# Power.net
KiCad netlist of a schematic drawn in Altium Designer
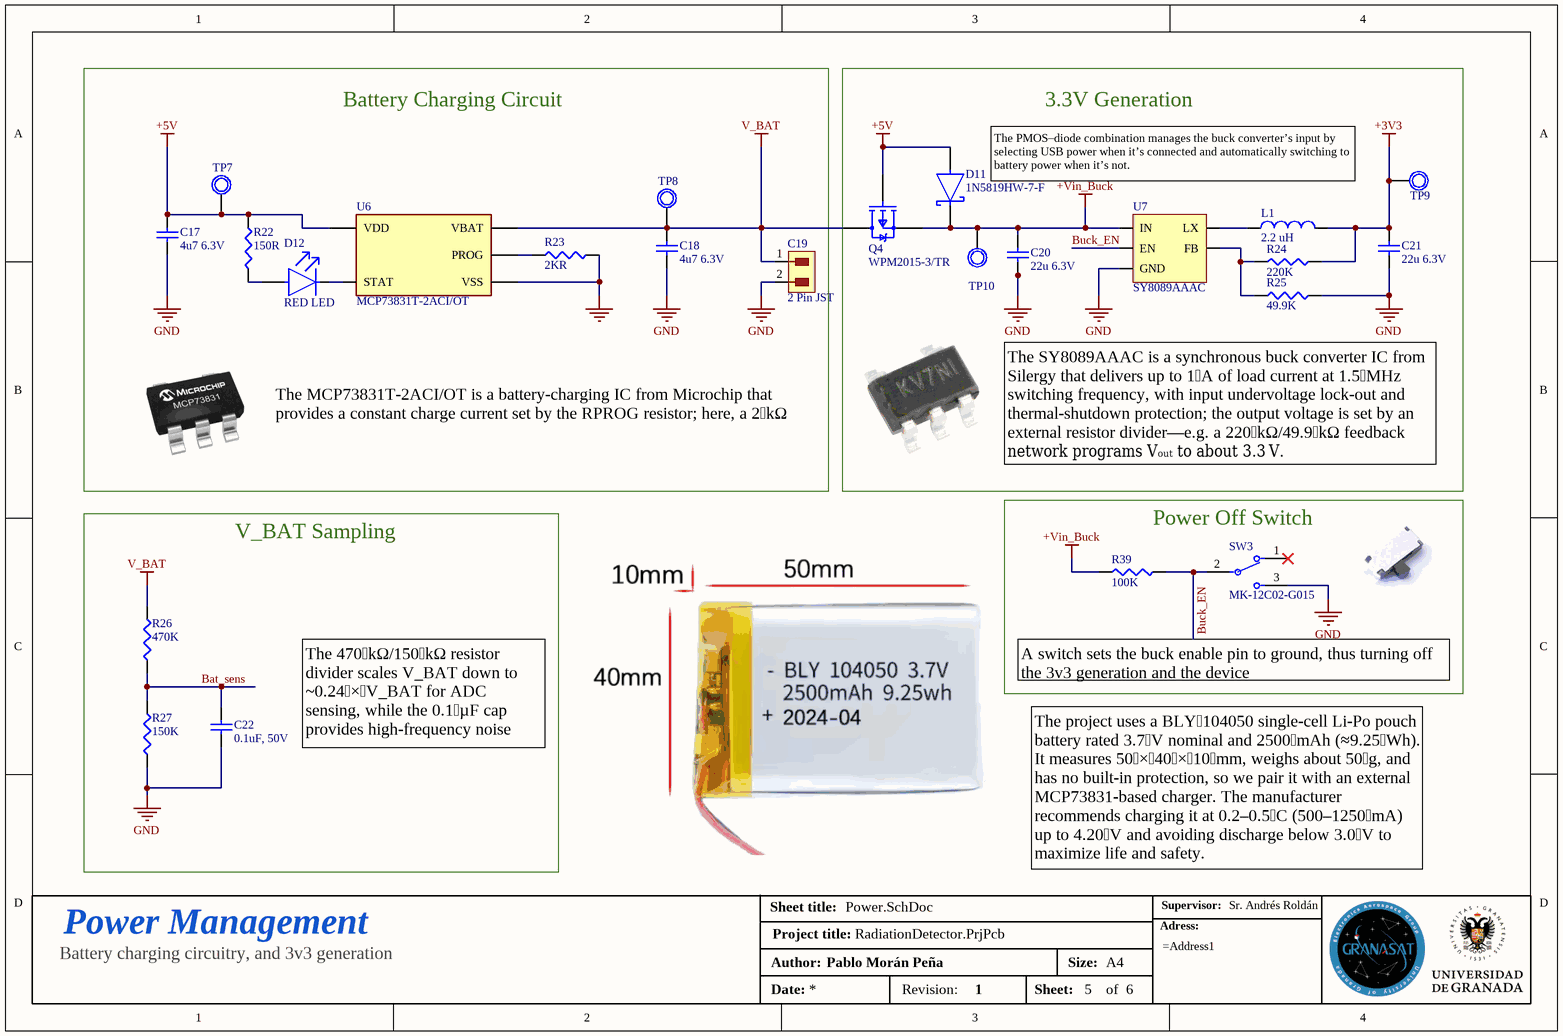
[diagram p0: Power.SchDoc]

(export (version "E")
  (design (tool "Eeschema 10.0.6"))
  (components
    (comp (ref "C17")
      (value "4u7 6.3V")
      (footprint "CAP 0402_1005")
      (description "CAP CER 4.7UF 6.3V X5R 0402")
      (fields
        (field (name "MANUFACTURER") "Samsung")
        (field (name "MANUFACTURER PART NUMBER") "CL05A475KQ5NRNC")
      )
      (libsource (lib "Schlib") (part "CL05A475KQ5NRNC"))
    )
    (comp (ref "C18")
      (value "4u7 6.3V")
      (footprint "CAP 0402_1005")
      (description "CAP CER 4.7UF 6.3V X5R 0402")
      (fields
        (field (name "MANUFACTURER") "Samsung")
        (field (name "MANUFACTURER PART NUMBER") "CL05A475KQ5NRNC")
      )
      (libsource (lib "Schlib") (part "CL05A475KQ5NRNC"))
    )
    (comp (ref "C19")
      (value "2 Pin JST")
      (footprint "JST_B2B-PH-K-S")
      (fields
        (field (name "MANUFACTURER") "JST")
        (field (name "MANUFACTURER PART NUMBER") "B2B-PH-K-S(LF)(SN)")
        (field (name "LCSC PART NUMBER") "C131337")
      )
      (libsource (lib "Schlib") (part "B2B-PH-K-S(LF)(SN)"))
    )
    (comp (ref "C20")
      (value "22u 6.3V")
      (footprint "CAPC1608X90")
      (description "CAP CER 22UF 6.3V X5R 0603")
      (fields
        (field (name "MANUFACTURER") "Samsung")
        (field (name "MANUFACTURER PART NUMBER") "CL10A226MQ8NRNC")
      )
      (libsource (lib "Schlib") (part "CL10A226MQ8NRNC"))
    )
    (comp (ref "C21")
      (value "22u 6.3V")
      (footprint "CAPC1608X90")
      (description "CAP CER 22UF 6.3V X5R 0603")
      (fields
        (field (name "MANUFACTURER") "Samsung")
        (field (name "MANUFACTURER PART NUMBER") "CL10A226MQ8NRNC")
      )
      (libsource (lib "Schlib") (part "CL10A226MQ8NRNC"))
    )
    (comp (ref "C22")
      (value "0.1uF, 50V")
      (footprint "CAP 0402_1005")
      (description "CAP CER 0.1UF 50V X7R 0402")
      (fields
        (field (name "MANUFACTURER") "Samsung")
        (field (name "MANUFACTURER PART NUMBER") "CL05B104KB5NNNC")
      )
      (libsource (lib "Schlib") (part "CL05B104KB5NNNC"))
    )
    (comp (ref "D11")
      (value "1N5819HW-7-F")
      (footprint "FP-SOD123-MFG")
      (description "DIODE SCHOTTKY 40V 1A SOD123")
      (fields (field (name "MANUFACTURER") "Diodes") (field (name "LCSC PART NUMBER") "C82544"))
      (libsource (lib "Schlib") (part "1N5819HW-7-F"))
    )
    (comp (ref "D12")
      (value "RED LED")
      (footprint "FP-LTST-C171KGKT-MFG")
      (description "LED RED CLEAR SMD")
      (fields
        (field (name "MANUFACTURER") "Vishay Lite-On")
        (field (name "MANUFACTURER PART NUMBER") "LTST-C171KGKT")
      )
      (libsource (lib "Schlib") (part "LTST-C171KGKT"))
    )
    (comp (ref "L1")
      (value "2.2 uH")
      (footprint "IND_VLS3015ET-220M-CA")
      (description "1.35A 2.2uH ±20% 1.35A SMD,3x3mm Power Inductors ROHS")
      (fields (field (name "MANUFACTURER") "TDK") (field (name "MANUFACTURER PART NUMBER") "VLS3015ET-2R2M"))
      (libsource (lib "Schlib") (part "VLS3015ET-2R2M"))
    )
    (comp (ref "Q4")
      (value "WPM2015-3/TR")
      (footprint "SOT-23")
      (description "20V 2.4A 110mΩ@4.5V,2.7A 1.1W 1V@250uA 1 P-Channel SOT-23-3 MOSFETs ROHS")
      (fields (field (name "LCSC PART NUMBER") "C6562215"))
      (libsource (lib "Schlib") (part "WPM2015-3/TR"))
    )
    (comp (ref "R22")
      (value "150R")
      (footprint "RESC1005X37N")
      (description "RES SMD 150 OHM 1% 1/16W 0402")
      (fields
        (field (name "MANUFACTURER") "Yageo")
        (field (name "MANUFACTURER PART NUMBER") "AC0402FR-07150RL")
      )
      (libsource (lib "Schlib") (part "AC0402FR-07150RL"))
    )
    (comp (ref "R23")
      (value "2KR")
      (footprint "RESC1005X37N")
      (description "RES 2K OHM 1% 1/16W 0402")
      (fields
        (field (name "MANUFACTURER") "Yageo")
        (field (name "MANUFACTURER PART NUMBER") "AC0402FR-132KL")
      )
      (libsource (lib "Schlib") (part "AC0402FR-132KL"))
    )
    (comp (ref "R24")
      (value "220K")
      (footprint "RESC1005X37N")
      (description "RES 220K OHM 5% 1/16W 0402")
      (fields
        (field (name "MANUFACTURER") "Yageo")
        (field (name "MANUFACTURER PART NUMBER") "RC0402JR-07220KL")
      )
      (libsource (lib "Schlib") (part "RC0402JR-07220KL"))
    )
    (comp (ref "R25")
      (value "49.9K")
      (footprint "RESC1005X37N")
      (description "RES 49.9K OHM 1% 1/16W 0402")
      (fields
        (field (name "MANUFACTURER") "Yageo")
        (field (name "MANUFACTURER PART NUMBER") "RC0402FR-0749K9L")
      )
      (libsource (lib "Schlib") (part "RC0402FR-0749K9L"))
    )
    (comp (ref "R26")
      (value "470K")
      (footprint "RESC1005X37N")
      (description "RES 470K OHM 5% 1/16W 0402")
      (fields
        (field (name "MANUFACTURER") "Yageo")
        (field (name "MANUFACTURER PART NUMBER") "RC0402JR-07470KL")
      )
      (libsource (lib "Schlib") (part "RC0402JR-07470KL"))
    )
    (comp (ref "R27")
      (value "150K")
      (footprint "RESC1005X37N")
      (description "RES 150K OHM 5% 1/16W 0402")
      (fields
        (field (name "MANUFACTURER") "Yageo")
        (field (name "MANUFACTURER PART NUMBER") "RC0402JR-07150KL")
      )
      (libsource (lib "Schlib") (part "RC0402JR-07150KL"))
    )
    (comp (ref "R39")
      (value "100K")
      (footprint "RESC1005X37N")
      (description "RES SMD 100K OHM 1% 1/16W 0402")
      (fields
        (field (name "MANUFACTURER") "Yageo")
        (field (name "MANUFACTURER PART NUMBER") "AC0402FR-07100KL")
      )
      (libsource (lib "Schlib") (part "AC0402FR-07100KL"))
    )
    (comp (ref "SW3")
      (value "MK-12C02-G015")
      (footprint "Switch")
      (description "Surface Mount, Right Angle 1A SPDT 6V Black 10,000 Cycles SMD Slide Switches ROHS")
      (fields (field (name "LCSC PART NUMBER") "C2911519"))
      (libsource (lib "Schlib") (part "MK-12C02-G015"))
    )
    (comp (ref "TP7")
      (value "Testpoint")
      (footprint "Testpoint")
      (libsource (lib "Schlib") (part "Testpoint"))
    )
    (comp (ref "TP8")
      (value "Testpoint")
      (footprint "Testpoint")
      (libsource (lib "Schlib") (part "Testpoint"))
    )
    (comp (ref "TP9")
      (value "Testpoint")
      (footprint "Testpoint")
      (libsource (lib "Schlib") (part "Testpoint"))
    )
    (comp (ref "TP10")
      (value "Testpoint")
      (footprint "Testpoint")
      (libsource (lib "Schlib") (part "Testpoint"))
    )
    (comp (ref "U6")
      (value "MCP73831T-2ACI/OT")
      (footprint "FP-C04-091-OT-IPC_B")
      (description "Power Supply Support Circuit, Adjustable, 1 Channel, PDSO5")
      (fields (field (name "MANUFACTURER") "Microchip") (field (name "LCSC PART NUMBER") "C424093"))
      (libsource (lib "Schlib") (part "MCP73831T-2ACI/OT"))
    )
    (comp (ref "U7")
      (value "SY8089AAAC")
      (footprint "SOT95P285X140-5N")
      (description "Buck Adjustable 2A 2.7V~5.5V SOT-23-5 DC-DC Converters ROHS")
      (fields (field (name "LCSC PART NUMBER") "C78988"))
      (libsource (lib "Schlib") (part "SY8089AAAC"))
    )
  )
  (nets
    (net (code "1") (name "+3V3") (class "Default")
      (node (ref "C21") (pin "2") (pinfunction "2_2") (pintype "passive"))
      (node (ref "L1") (pin "2") (pinfunction "2_2") (pintype "passive"))
      (node (ref "R24") (pin "2") (pinfunction "2_2") (pintype "passive"))
      (node (ref "TP9") (pin "1") (pinfunction "1_1") (pintype "passive"))
    )
    (net (code "2") (name "+5V") (class "Default")
      (node (ref "C17") (pin "2") (pinfunction "2_2") (pintype "passive"))
      (node (ref "D11") (pin "2") (pinfunction "A_2") (pintype "passive"))
      (node (ref "Q4") (pin "1") (pinfunction "G_1") (pintype "passive"))
      (node (ref "R22") (pin "2") (pinfunction "2_2") (pintype "passive"))
      (node (ref "TP7") (pin "1") (pinfunction "1_1") (pintype "passive"))
      (node (ref "U6") (pin "4") (pinfunction "VDD_4") (pintype "power_in"))
    )
    (net (code "3") (name "+Vin_Buck") (class "Default")
      (node (ref "C20") (pin "2") (pinfunction "2_2") (pintype "passive"))
      (node (ref "D11") (pin "1") (pinfunction "C_1") (pintype "passive"))
      (node (ref "Q4") (pin "2") (pinfunction "S_2") (pintype "passive"))
      (node (ref "R39") (pin "1") (pinfunction "1_1") (pintype "passive"))
      (node (ref "TP10") (pin "1") (pinfunction "1_1") (pintype "passive"))
      (node (ref "U7") (pin "4") (pinfunction "IN_4") (pintype "passive"))
    )
    (net (code "4") (name "/Bat_sens") (class "Default")
      (node (ref "C22") (pin "2") (pinfunction "2_2") (pintype "passive"))
      (node (ref "R26") (pin "1") (pinfunction "1_1") (pintype "passive"))
      (node (ref "R27") (pin "1") (pinfunction "1_1") (pintype "passive"))
    )
    (net (code "5") (name "/Buck_EN") (class "Default")
      (node (ref "R39") (pin "2") (pinfunction "2_2") (pintype "passive"))
      (node (ref "SW3") (pin "2") (pinfunction "C_2") (pintype "passive"))
      (node (ref "U7") (pin "1") (pinfunction "EN_1") (pintype "passive"))
    )
    (net (code "6") (name "GND") (class "Default")
      (node (ref "C17") (pin "1") (pinfunction "1_1") (pintype "passive"))
      (node (ref "C18") (pin "1") (pinfunction "1_1") (pintype "passive"))
      (node (ref "C19") (pin "2") (pinfunction "2_2") (pintype "passive"))
      (node (ref "C20") (pin "1") (pinfunction "1_1") (pintype "passive"))
      (node (ref "C21") (pin "1") (pinfunction "1_1") (pintype "passive"))
      (node (ref "C22") (pin "1") (pinfunction "1_1") (pintype "passive"))
      (node (ref "R23") (pin "2") (pinfunction "2_2") (pintype "passive"))
      (node (ref "R25") (pin "2") (pinfunction "2_2") (pintype "passive"))
      (node (ref "R27") (pin "2") (pinfunction "2_2") (pintype "passive"))
      (node (ref "SW3") (pin "3") (pinfunction "3_3") (pintype "passive"))
      (node (ref "U6") (pin "2") (pinfunction "VSS_2") (pintype "power_in"))
      (node (ref "U7") (pin "2") (pinfunction "GND_2") (pintype "passive"))
    )
    (net (code "7") (name "Net-(D12-A)") (class "Default")
      (node (ref "D12") (pin "2") (pinfunction "A_2") (pintype "passive"))
      (node (ref "R22") (pin "1") (pinfunction "1_1") (pintype "passive"))
    )
    (net (code "8") (name "Net-(D12-C)") (class "Default")
      (node (ref "D12") (pin "1") (pinfunction "C_1") (pintype "passive"))
      (node (ref "U6") (pin "1") (pinfunction "STAT_1") (pintype "passive"))
    )
    (net (code "9") (name "Net-(U6-PROG)") (class "Default")
      (node (ref "R23") (pin "1") (pinfunction "1_1") (pintype "passive"))
      (node (ref "U6") (pin "5") (pinfunction "PROG_5") (pintype "passive"))
    )
    (net (code "10") (name "Net-(U7-FB)") (class "Default")
      (node (ref "R24") (pin "1") (pinfunction "1_1") (pintype "passive"))
      (node (ref "R25") (pin "1") (pinfunction "1_1") (pintype "passive"))
      (node (ref "U7") (pin "5") (pinfunction "FB_5") (pintype "passive"))
    )
    (net (code "11") (name "Net-(U7-LX)") (class "Default")
      (node (ref "L1") (pin "1") (pinfunction "1_1") (pintype "passive"))
      (node (ref "U7") (pin "3") (pinfunction "LX_3") (pintype "passive"))
    )
    (net (code "12") (name "V_BAT") (class "Default")
      (node (ref "C18") (pin "2") (pinfunction "2_2") (pintype "passive"))
      (node (ref "C19") (pin "1") (pinfunction "1_1") (pintype "passive"))
      (node (ref "Q4") (pin "3") (pinfunction "D_3") (pintype "passive"))
      (node (ref "R26") (pin "2") (pinfunction "2_2") (pintype "passive"))
      (node (ref "TP8") (pin "1") (pinfunction "1_1") (pintype "passive"))
      (node (ref "U6") (pin "3") (pinfunction "VBAT_3") (pintype "power_in"))
    )
    (net (code "13") (name "unconnected-(SW3-Pad1)") (class "Default")
      (node (ref "SW3") (pin "1") (pinfunction "1_1") (pintype "passive+no_connect"))
    )
  )
)
